# OldLineFollowerRecreate.net
KiCad netlist of a schematic drawn in EAGLE
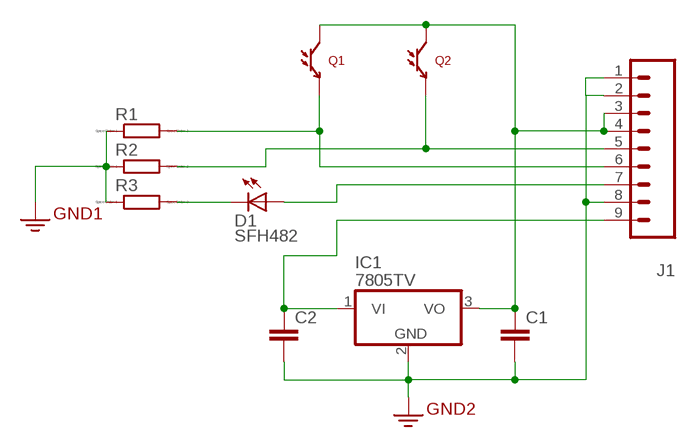
[diagram p0: schematic, sheet 1]

(export (version "E")
  (design (tool "Eeschema 10.0.6"))
  (components
    (comp (ref "C1")
      (value "C2.5/5")
      (footprint "eagle-import:C2.5-5")
      (libsource (lib "eagle-import") (part "C2.5/5"))
    )
    (comp (ref "C2")
      (value "C2.5/5")
      (footprint "eagle-import:C2.5-5")
      (libsource (lib "eagle-import") (part "C2.5/5"))
    )
    (comp (ref "D1")
      (value "SFH482")
      (footprint "eagle-import:SFH482")
      (libsource (lib "eagle-import") (part "SFH482"))
    )
    (comp (ref "IC1")
      (value "7805TV")
      (footprint "eagle-import:TO220V")
      (libsource (lib "eagle-import") (part "78TV05"))
    )
    (comp (ref "J1")
      (value "M09")
      (footprint "eagle-import:1X09")
      (libsource (lib "eagle-import") (part "M09"))
    )
    (comp (ref "Q1")
      (value "LTR-301")
      (footprint "eagle-import:LTR-301")
      (libsource (lib "eagle-import") (part "LTR-301"))
    )
    (comp (ref "Q2")
      (value "LTR-301")
      (footprint "eagle-import:LTR-301")
      (libsource (lib "eagle-import") (part "LTR-301"))
    )
    (comp (ref "R1")
      (value "R0204/7")
      (footprint "eagle-import:0204_7")
      (libsource (lib "eagle-import") (part "R0204/7"))
    )
    (comp (ref "R2")
      (value "R0204/7")
      (footprint "eagle-import:0204_7")
      (libsource (lib "eagle-import") (part "R0204/7"))
    )
    (comp (ref "R3")
      (value "R0204/7")
      (footprint "eagle-import:0204_7")
      (libsource (lib "eagle-import") (part "R0204/7"))
    )
  )
  (nets
    (net (code "1") (name "GND2") (class "Default")
      (node (ref "C1") (pin "2") (pinfunction "2_2") (pintype "passive"))
      (node (ref "C2") (pin "2") (pinfunction "2_2") (pintype "passive"))
      (node (ref "IC1") (pin "2") (pinfunction "GND_2") (pintype "passive"))
      (node (ref "J1") (pin "1") (pinfunction "1_1") (pintype "passive"))
      (node (ref "J1") (pin "2") (pinfunction "2_2") (pintype "passive"))
      (node (ref "J1") (pin "8") (pinfunction "8_8") (pintype "passive"))
      (node (ref "R1") (pin "1") (pinfunction "1_1") (pintype "passive"))
      (node (ref "R2") (pin "1") (pinfunction "1_1") (pintype "passive"))
      (node (ref "R3") (pin "1") (pinfunction "1_1") (pintype "passive"))
    )
    (net (code "2") (name "Net-(D1-C)") (class "Default")
      (node (ref "D1") (pin "K") (pinfunction "C_K") (pintype "passive"))
      (node (ref "R3") (pin "2") (pinfunction "2_2") (pintype "passive"))
    )
    (net (code "3") (name "Net-(D1-PadA)") (class "Default")
      (node (ref "D1") (pin "A") (pinfunction "A_A") (pintype "passive"))
      (node (ref "J1") (pin "7") (pinfunction "7_7") (pintype "passive"))
    )
    (net (code "4") (name "Net-(IC1-VI)") (class "Default")
      (node (ref "C2") (pin "1") (pinfunction "1_1") (pintype "passive"))
      (node (ref "IC1") (pin "1") (pinfunction "VI_1") (pintype "input"))
      (node (ref "J1") (pin "9") (pinfunction "9_9") (pintype "passive"))
    )
    (net (code "5") (name "Net-(IC1-VO)") (class "Default")
      (node (ref "C1") (pin "1") (pinfunction "1_1") (pintype "passive"))
      (node (ref "IC1") (pin "3") (pinfunction "VO_3") (pintype "passive"))
      (node (ref "J1") (pin "3") (pinfunction "3_3") (pintype "passive"))
      (node (ref "J1") (pin "4") (pinfunction "4_4") (pintype "passive"))
      (node (ref "Q1") (pin "C") (pinfunction "C_C") (pintype "bidirectional"))
      (node (ref "Q2") (pin "C") (pinfunction "C_C") (pintype "bidirectional"))
    )
    (net (code "6") (name "Net-(J1-Pad5)") (class "Default")
      (node (ref "J1") (pin "5") (pinfunction "5_5") (pintype "passive"))
      (node (ref "Q2") (pin "E") (pinfunction "E_E") (pintype "bidirectional"))
      (node (ref "R2") (pin "2") (pinfunction "2_2") (pintype "passive"))
    )
    (net (code "7") (name "Net-(J1-Pad6)") (class "Default")
      (node (ref "J1") (pin "6") (pinfunction "6_6") (pintype "passive"))
      (node (ref "Q1") (pin "E") (pinfunction "E_E") (pintype "bidirectional"))
      (node (ref "R1") (pin "2") (pinfunction "2_2") (pintype "passive"))
    )
  )
)
